# BMW_Front-Centet_Driver-Passenger_Light.net
KiCad netlist of a schematic drawn in Altium Designer
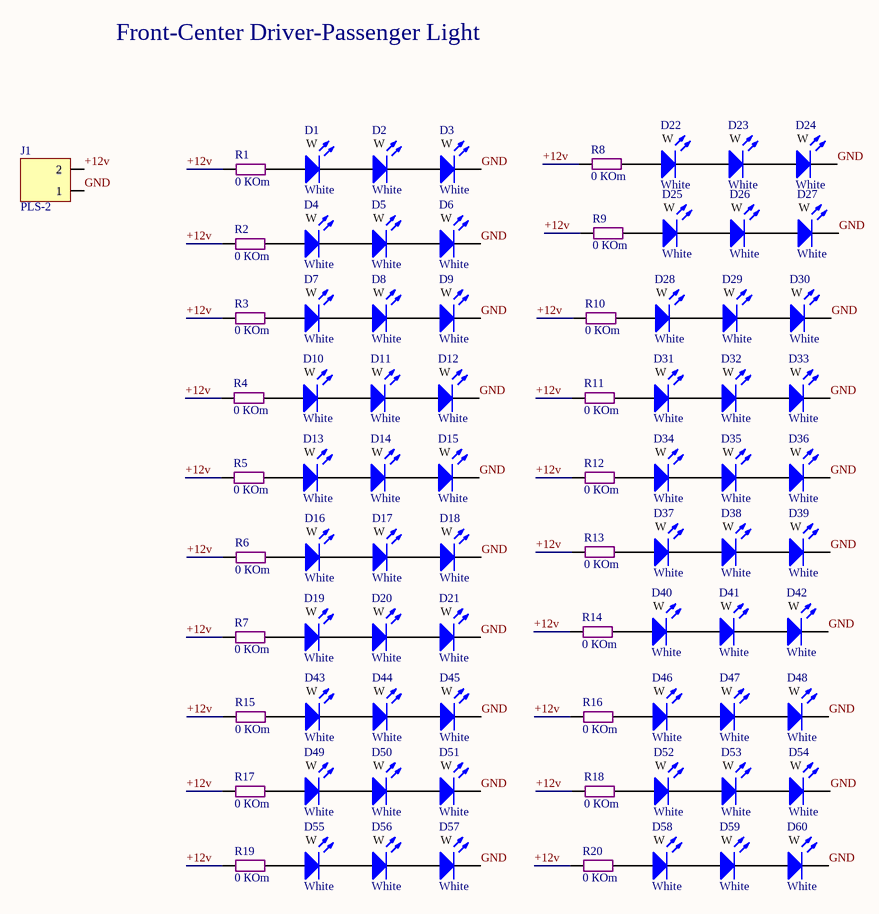
[diagram p0: BMW Front-Centet Driver-Passenger Light.SchDoc]

(export (version "E")
  (design (tool "Eeschema 10.0.6"))
  (components
    (comp (ref "D1")
      (value "White")
      (footprint "LED:LED Round 5mm White")
      (description "3.2-3.4v 25mA, 16-20cd")
      (libsource (lib "LED") (part "Led Round 5mm White"))
    )
    (comp (ref "D2")
      (value "White")
      (footprint "LED:LED Round 5mm White")
      (description "3.2-3.4v 25mA, 16-20cd")
      (libsource (lib "LED") (part "Led Round 5mm White"))
    )
    (comp (ref "D3")
      (value "White")
      (footprint "LED:LED Round 5mm White")
      (description "3.2-3.4v 25mA, 16-20cd")
      (libsource (lib "LED") (part "Led Round 5mm White"))
    )
    (comp (ref "D4")
      (value "White")
      (footprint "LED:LED Round 5mm White")
      (description "3.2-3.4v 25mA, 16-20cd")
      (libsource (lib "LED") (part "Led Round 5mm White"))
    )
    (comp (ref "D5")
      (value "White")
      (footprint "LED:LED Round 5mm White")
      (description "3.2-3.4v 25mA, 16-20cd")
      (libsource (lib "LED") (part "Led Round 5mm White"))
    )
    (comp (ref "D6")
      (value "White")
      (footprint "LED:LED Round 5mm White")
      (description "3.2-3.4v 25mA, 16-20cd")
      (libsource (lib "LED") (part "Led Round 5mm White"))
    )
    (comp (ref "D7")
      (value "White")
      (footprint "LED:LED Round 5mm White")
      (description "3.2-3.4v 25mA, 16-20cd")
      (libsource (lib "LED") (part "Led Round 5mm White"))
    )
    (comp (ref "D8")
      (value "White")
      (footprint "LED:LED Round 5mm White")
      (description "3.2-3.4v 25mA, 16-20cd")
      (libsource (lib "LED") (part "Led Round 5mm White"))
    )
    (comp (ref "D9")
      (value "White")
      (footprint "LED:LED Round 5mm White")
      (description "3.2-3.4v 25mA, 16-20cd")
      (libsource (lib "LED") (part "Led Round 5mm White"))
    )
    (comp (ref "D10")
      (value "White")
      (footprint "LED:LED Round 5mm White")
      (description "3.2-3.4v 25mA, 16-20cd")
      (libsource (lib "LED") (part "Led Round 5mm White"))
    )
    (comp (ref "D11")
      (value "White")
      (footprint "LED:LED Round 5mm White")
      (description "3.2-3.4v 25mA, 16-20cd")
      (libsource (lib "LED") (part "Led Round 5mm White"))
    )
    (comp (ref "D12")
      (value "White")
      (footprint "LED:LED Round 5mm White")
      (description "3.2-3.4v 25mA, 16-20cd")
      (libsource (lib "LED") (part "Led Round 5mm White"))
    )
    (comp (ref "D13")
      (value "White")
      (footprint "LED:LED Round 5mm White")
      (description "3.2-3.4v 25mA, 16-20cd")
      (libsource (lib "LED") (part "Led Round 5mm White"))
    )
    (comp (ref "D14")
      (value "White")
      (footprint "LED:LED Round 5mm White")
      (description "3.2-3.4v 25mA, 16-20cd")
      (libsource (lib "LED") (part "Led Round 5mm White"))
    )
    (comp (ref "D15")
      (value "White")
      (footprint "LED:LED Round 5mm White")
      (description "3.2-3.4v 25mA, 16-20cd")
      (libsource (lib "LED") (part "Led Round 5mm White"))
    )
    (comp (ref "D16")
      (value "White")
      (footprint "LED:LED Round 5mm White")
      (description "3.2-3.4v 25mA, 16-20cd")
      (libsource (lib "LED") (part "Led Round 5mm White"))
    )
    (comp (ref "D17")
      (value "White")
      (footprint "LED:LED Round 5mm White")
      (description "3.2-3.4v 25mA, 16-20cd")
      (libsource (lib "LED") (part "Led Round 5mm White"))
    )
    (comp (ref "D18")
      (value "White")
      (footprint "LED:LED Round 5mm White")
      (description "3.2-3.4v 25mA, 16-20cd")
      (libsource (lib "LED") (part "Led Round 5mm White"))
    )
    (comp (ref "D19")
      (value "White")
      (footprint "LED:LED Round 5mm White")
      (description "3.2-3.4v 25mA, 16-20cd")
      (libsource (lib "LED") (part "Led Round 5mm White"))
    )
    (comp (ref "D20")
      (value "White")
      (footprint "LED:LED Round 5mm White")
      (description "3.2-3.4v 25mA, 16-20cd")
      (libsource (lib "LED") (part "Led Round 5mm White"))
    )
    (comp (ref "D21")
      (value "White")
      (footprint "LED:LED Round 5mm White")
      (description "3.2-3.4v 25mA, 16-20cd")
      (libsource (lib "LED") (part "Led Round 5mm White"))
    )
    (comp (ref "D22")
      (value "White")
      (footprint "LED:LED Round 5mm White")
      (description "3.2-3.4v 25mA, 16-20cd")
      (libsource (lib "LED") (part "Led Round 5mm White"))
    )
    (comp (ref "D23")
      (value "White")
      (footprint "LED:LED Round 5mm White")
      (description "3.2-3.4v 25mA, 16-20cd")
      (libsource (lib "LED") (part "Led Round 5mm White"))
    )
    (comp (ref "D24")
      (value "White")
      (footprint "LED:LED Round 5mm White")
      (description "3.2-3.4v 25mA, 16-20cd")
      (libsource (lib "LED") (part "Led Round 5mm White"))
    )
    (comp (ref "D25")
      (value "White")
      (footprint "LED:LED Round 5mm White")
      (description "3.2-3.4v 25mA, 16-20cd")
      (libsource (lib "LED") (part "Led Round 5mm White"))
    )
    (comp (ref "D26")
      (value "White")
      (footprint "LED:LED Round 5mm White")
      (description "3.2-3.4v 25mA, 16-20cd")
      (libsource (lib "LED") (part "Led Round 5mm White"))
    )
    (comp (ref "D27")
      (value "White")
      (footprint "LED:LED Round 5mm White")
      (description "3.2-3.4v 25mA, 16-20cd")
      (libsource (lib "LED") (part "Led Round 5mm White"))
    )
    (comp (ref "D28")
      (value "White")
      (footprint "LED:LED Round 5mm White")
      (description "3.2-3.4v 25mA, 16-20cd")
      (libsource (lib "LED") (part "Led Round 5mm White"))
    )
    (comp (ref "D29")
      (value "White")
      (footprint "LED:LED Round 5mm White")
      (description "3.2-3.4v 25mA, 16-20cd")
      (libsource (lib "LED") (part "Led Round 5mm White"))
    )
    (comp (ref "D30")
      (value "White")
      (footprint "LED:LED Round 5mm White")
      (description "3.2-3.4v 25mA, 16-20cd")
      (libsource (lib "LED") (part "Led Round 5mm White"))
    )
    (comp (ref "D31")
      (value "White")
      (footprint "LED:LED Round 5mm White")
      (description "3.2-3.4v 25mA, 16-20cd")
      (libsource (lib "LED") (part "Led Round 5mm White"))
    )
    (comp (ref "D32")
      (value "White")
      (footprint "LED:LED Round 5mm White")
      (description "3.2-3.4v 25mA, 16-20cd")
      (libsource (lib "LED") (part "Led Round 5mm White"))
    )
    (comp (ref "D33")
      (value "White")
      (footprint "LED:LED Round 5mm White")
      (description "3.2-3.4v 25mA, 16-20cd")
      (libsource (lib "LED") (part "Led Round 5mm White"))
    )
    (comp (ref "D34")
      (value "White")
      (footprint "LED:LED Round 5mm White")
      (description "3.2-3.4v 25mA, 16-20cd")
      (libsource (lib "LED") (part "Led Round 5mm White"))
    )
    (comp (ref "D35")
      (value "White")
      (footprint "LED:LED Round 5mm White")
      (description "3.2-3.4v 25mA, 16-20cd")
      (libsource (lib "LED") (part "Led Round 5mm White"))
    )
    (comp (ref "D36")
      (value "White")
      (footprint "LED:LED Round 5mm White")
      (description "3.2-3.4v 25mA, 16-20cd")
      (libsource (lib "LED") (part "Led Round 5mm White"))
    )
    (comp (ref "D37")
      (value "White")
      (footprint "LED:LED Round 5mm White")
      (description "3.2-3.4v 25mA, 16-20cd")
      (libsource (lib "LED") (part "Led Round 5mm White"))
    )
    (comp (ref "D38")
      (value "White")
      (footprint "LED:LED Round 5mm White")
      (description "3.2-3.4v 25mA, 16-20cd")
      (libsource (lib "LED") (part "Led Round 5mm White"))
    )
    (comp (ref "D39")
      (value "White")
      (footprint "LED:LED Round 5mm White")
      (description "3.2-3.4v 25mA, 16-20cd")
      (libsource (lib "LED") (part "Led Round 5mm White"))
    )
    (comp (ref "D40")
      (value "White")
      (footprint "LED:LED Round 5mm White")
      (description "3.2-3.4v 25mA, 16-20cd")
      (libsource (lib "LED") (part "Led Round 5mm White"))
    )
    (comp (ref "D41")
      (value "White")
      (footprint "LED:LED Round 5mm White")
      (description "3.2-3.4v 25mA, 16-20cd")
      (libsource (lib "LED") (part "Led Round 5mm White"))
    )
    (comp (ref "D42")
      (value "White")
      (footprint "LED:LED Round 5mm White")
      (description "3.2-3.4v 25mA, 16-20cd")
      (libsource (lib "LED") (part "Led Round 5mm White"))
    )
    (comp (ref "D43")
      (value "White")
      (footprint "LED:LED Round 5mm White")
      (description "3.2-3.4v 25mA, 16-20cd")
      (libsource (lib "LED") (part "Led Round 5mm White"))
    )
    (comp (ref "D44")
      (value "White")
      (footprint "LED:LED Round 5mm White")
      (description "3.2-3.4v 25mA, 16-20cd")
      (libsource (lib "LED") (part "Led Round 5mm White"))
    )
    (comp (ref "D45")
      (value "White")
      (footprint "LED:LED Round 5mm White")
      (description "3.2-3.4v 25mA, 16-20cd")
      (libsource (lib "LED") (part "Led Round 5mm White"))
    )
    (comp (ref "D46")
      (value "White")
      (footprint "LED:LED Round 5mm White")
      (description "3.2-3.4v 25mA, 16-20cd")
      (libsource (lib "LED") (part "Led Round 5mm White"))
    )
    (comp (ref "D47")
      (value "White")
      (footprint "LED:LED Round 5mm White")
      (description "3.2-3.4v 25mA, 16-20cd")
      (libsource (lib "LED") (part "Led Round 5mm White"))
    )
    (comp (ref "D48")
      (value "White")
      (footprint "LED:LED Round 5mm White")
      (description "3.2-3.4v 25mA, 16-20cd")
      (libsource (lib "LED") (part "Led Round 5mm White"))
    )
    (comp (ref "D49")
      (value "White")
      (footprint "LED:LED Round 5mm White")
      (description "3.2-3.4v 25mA, 16-20cd")
      (libsource (lib "LED") (part "Led Round 5mm White"))
    )
    (comp (ref "D50")
      (value "White")
      (footprint "LED:LED Round 5mm White")
      (description "3.2-3.4v 25mA, 16-20cd")
      (libsource (lib "LED") (part "Led Round 5mm White"))
    )
    (comp (ref "D51")
      (value "White")
      (footprint "LED:LED Round 5mm White")
      (description "3.2-3.4v 25mA, 16-20cd")
      (libsource (lib "LED") (part "Led Round 5mm White"))
    )
    (comp (ref "D52")
      (value "White")
      (footprint "LED:LED Round 5mm White")
      (description "3.2-3.4v 25mA, 16-20cd")
      (libsource (lib "LED") (part "Led Round 5mm White"))
    )
    (comp (ref "D53")
      (value "White")
      (footprint "LED:LED Round 5mm White")
      (description "3.2-3.4v 25mA, 16-20cd")
      (libsource (lib "LED") (part "Led Round 5mm White"))
    )
    (comp (ref "D54")
      (value "White")
      (footprint "LED:LED Round 5mm White")
      (description "3.2-3.4v 25mA, 16-20cd")
      (libsource (lib "LED") (part "Led Round 5mm White"))
    )
    (comp (ref "D55")
      (value "White")
      (footprint "LED:LED Round 5mm White")
      (description "3.2-3.4v 25mA, 16-20cd")
      (libsource (lib "LED") (part "Led Round 5mm White"))
    )
    (comp (ref "D56")
      (value "White")
      (footprint "LED:LED Round 5mm White")
      (description "3.2-3.4v 25mA, 16-20cd")
      (libsource (lib "LED") (part "Led Round 5mm White"))
    )
    (comp (ref "D57")
      (value "White")
      (footprint "LED:LED Round 5mm White")
      (description "3.2-3.4v 25mA, 16-20cd")
      (libsource (lib "LED") (part "Led Round 5mm White"))
    )
    (comp (ref "D58")
      (value "White")
      (footprint "LED:LED Round 5mm White")
      (description "3.2-3.4v 25mA, 16-20cd")
      (libsource (lib "LED") (part "Led Round 5mm White"))
    )
    (comp (ref "D59")
      (value "White")
      (footprint "LED:LED Round 5mm White")
      (description "3.2-3.4v 25mA, 16-20cd")
      (libsource (lib "LED") (part "Led Round 5mm White"))
    )
    (comp (ref "D60")
      (value "White")
      (footprint "LED:LED Round 5mm White")
      (description "3.2-3.4v 25mA, 16-20cd")
      (libsource (lib "LED") (part "Led Round 5mm White"))
    )
    (comp (ref "J1")
      (value "PLS-2")
      (footprint "Connector:Line 2.54 x 2")
      (description "Vert, Sgl line, Male")
      (libsource (lib "Connector") (part "PLS-2"))
    )
    (comp (ref "R1")
      (value "0 КOm")
      (footprint "bj Lib:SMD 0603 (1608)")
      (libsource (lib "ss_ServersControl") (part "Resistor"))
    )
    (comp (ref "R2")
      (value "0 КOm")
      (footprint "bj Lib:SMD 0603 (1608)")
      (libsource (lib "ss_ServersControl") (part "Resistor"))
    )
    (comp (ref "R3")
      (value "0 КOm")
      (footprint "bj Lib:SMD 0603 (1608)")
      (libsource (lib "ss_ServersControl") (part "Resistor"))
    )
    (comp (ref "R4")
      (value "0 КOm")
      (footprint "bj Lib:SMD 0603 (1608)")
      (libsource (lib "ss_ServersControl") (part "Resistor"))
    )
    (comp (ref "R5")
      (value "0 КOm")
      (footprint "bj Lib:SMD 0603 (1608)")
      (libsource (lib "ss_ServersControl") (part "Resistor"))
    )
    (comp (ref "R6")
      (value "0 КOm")
      (footprint "bj Lib:SMD 0603 (1608)")
      (libsource (lib "ss_ServersControl") (part "Resistor"))
    )
    (comp (ref "R7")
      (value "0 КOm")
      (footprint "bj Lib:SMD 0603 (1608)")
      (libsource (lib "ss_ServersControl") (part "Resistor"))
    )
    (comp (ref "R8")
      (value "0 КOm")
      (footprint "bj Lib:SMD 0603 (1608)")
      (libsource (lib "ss_ServersControl") (part "Resistor"))
    )
    (comp (ref "R9")
      (value "0 КOm")
      (footprint "bj Lib:SMD 0603 (1608)")
      (libsource (lib "ss_ServersControl") (part "Resistor"))
    )
    (comp (ref "R10")
      (value "0 КOm")
      (footprint "bj Lib:SMD 0603 (1608)")
      (libsource (lib "ss_ServersControl") (part "Resistor"))
    )
    (comp (ref "R11")
      (value "0 КOm")
      (footprint "bj Lib:SMD 0603 (1608)")
      (libsource (lib "ss_ServersControl") (part "Resistor"))
    )
    (comp (ref "R12")
      (value "0 КOm")
      (footprint "bj Lib:SMD 0603 (1608)")
      (libsource (lib "ss_ServersControl") (part "Resistor"))
    )
    (comp (ref "R13")
      (value "0 КOm")
      (footprint "bj Lib:SMD 0603 (1608)")
      (libsource (lib "ss_ServersControl") (part "Resistor"))
    )
    (comp (ref "R14")
      (value "0 КOm")
      (footprint "bj Lib:SMD 0603 (1608)")
      (libsource (lib "ss_ServersControl") (part "Resistor"))
    )
    (comp (ref "R15")
      (value "0 КOm")
      (footprint "bj Lib:SMD 0603 (1608)")
      (libsource (lib "ss_ServersControl") (part "Resistor"))
    )
    (comp (ref "R16")
      (value "0 КOm")
      (footprint "bj Lib:SMD 0603 (1608)")
      (libsource (lib "ss_ServersControl") (part "Resistor"))
    )
    (comp (ref "R17")
      (value "0 КOm")
      (footprint "bj Lib:SMD 0603 (1608)")
      (libsource (lib "ss_ServersControl") (part "Resistor"))
    )
    (comp (ref "R18")
      (value "0 КOm")
      (footprint "bj Lib:SMD 0603 (1608)")
      (libsource (lib "ss_ServersControl") (part "Resistor"))
    )
    (comp (ref "R19")
      (value "0 КOm")
      (footprint "bj Lib:SMD 0603 (1608)")
      (libsource (lib "ss_ServersControl") (part "Resistor"))
    )
    (comp (ref "R20")
      (value "0 КOm")
      (footprint "bj Lib:SMD 0603 (1608)")
      (libsource (lib "ss_ServersControl") (part "Resistor"))
    )
  )
  (nets
    (net (code "1") (name "/+12v") (class "Default")
      (node (ref "J1") (pin "2") (pinfunction "2_2") (pintype "passive"))
      (node (ref "R1") (pin "1") (pinfunction "1_1") (pintype "passive"))
      (node (ref "R10") (pin "1") (pinfunction "1_1") (pintype "passive"))
      (node (ref "R11") (pin "1") (pinfunction "1_1") (pintype "passive"))
      (node (ref "R12") (pin "1") (pinfunction "1_1") (pintype "passive"))
      (node (ref "R13") (pin "1") (pinfunction "1_1") (pintype "passive"))
      (node (ref "R14") (pin "1") (pinfunction "1_1") (pintype "passive"))
      (node (ref "R15") (pin "1") (pinfunction "1_1") (pintype "passive"))
      (node (ref "R16") (pin "1") (pinfunction "1_1") (pintype "passive"))
      (node (ref "R17") (pin "1") (pinfunction "1_1") (pintype "passive"))
      (node (ref "R18") (pin "1") (pinfunction "1_1") (pintype "passive"))
      (node (ref "R19") (pin "1") (pinfunction "1_1") (pintype "passive"))
      (node (ref "R2") (pin "1") (pinfunction "1_1") (pintype "passive"))
      (node (ref "R20") (pin "1") (pinfunction "1_1") (pintype "passive"))
      (node (ref "R3") (pin "1") (pinfunction "1_1") (pintype "passive"))
      (node (ref "R4") (pin "1") (pinfunction "1_1") (pintype "passive"))
      (node (ref "R5") (pin "1") (pinfunction "1_1") (pintype "passive"))
      (node (ref "R6") (pin "1") (pinfunction "1_1") (pintype "passive"))
      (node (ref "R7") (pin "1") (pinfunction "1_1") (pintype "passive"))
      (node (ref "R8") (pin "1") (pinfunction "1_1") (pintype "passive"))
      (node (ref "R9") (pin "1") (pinfunction "1_1") (pintype "passive"))
    )
    (net (code "2") (name "/GND") (class "Default")
      (node (ref "D12") (pin "K") (pinfunction "K_K") (pintype "passive"))
      (node (ref "D15") (pin "K") (pinfunction "K_K") (pintype "passive"))
      (node (ref "D18") (pin "K") (pinfunction "K_K") (pintype "passive"))
      (node (ref "D21") (pin "K") (pinfunction "K_K") (pintype "passive"))
      (node (ref "D24") (pin "K") (pinfunction "K_K") (pintype "passive"))
      (node (ref "D27") (pin "K") (pinfunction "K_K") (pintype "passive"))
      (node (ref "D3") (pin "K") (pinfunction "K_K") (pintype "passive"))
      (node (ref "D30") (pin "K") (pinfunction "K_K") (pintype "passive"))
      (node (ref "D33") (pin "K") (pinfunction "K_K") (pintype "passive"))
      (node (ref "D36") (pin "K") (pinfunction "K_K") (pintype "passive"))
      (node (ref "D39") (pin "K") (pinfunction "K_K") (pintype "passive"))
      (node (ref "D42") (pin "K") (pinfunction "K_K") (pintype "passive"))
      (node (ref "D45") (pin "K") (pinfunction "K_K") (pintype "passive"))
      (node (ref "D48") (pin "K") (pinfunction "K_K") (pintype "passive"))
      (node (ref "D51") (pin "K") (pinfunction "K_K") (pintype "passive"))
      (node (ref "D54") (pin "K") (pinfunction "K_K") (pintype "passive"))
      (node (ref "D57") (pin "K") (pinfunction "K_K") (pintype "passive"))
      (node (ref "D6") (pin "K") (pinfunction "K_K") (pintype "passive"))
      (node (ref "D60") (pin "K") (pinfunction "K_K") (pintype "passive"))
      (node (ref "D9") (pin "K") (pinfunction "K_K") (pintype "passive"))
      (node (ref "J1") (pin "1") (pinfunction "1_1") (pintype "passive"))
    )
    (net (code "3") (name "Net-(D1-PadA)") (class "Default")
      (node (ref "D1") (pin "A") (pinfunction "A_A") (pintype "passive"))
      (node (ref "R1") (pin "2") (pinfunction "2_2") (pintype "passive"))
    )
    (net (code "4") (name "Net-(D1-PadK)") (class "Default")
      (node (ref "D1") (pin "K") (pinfunction "K_K") (pintype "passive"))
      (node (ref "D2") (pin "A") (pinfunction "A_A") (pintype "passive"))
    )
    (net (code "5") (name "Net-(D2-PadK)") (class "Default")
      (node (ref "D2") (pin "K") (pinfunction "K_K") (pintype "passive"))
      (node (ref "D3") (pin "A") (pinfunction "A_A") (pintype "passive"))
    )
    (net (code "6") (name "Net-(D4-PadA)") (class "Default")
      (node (ref "D4") (pin "A") (pinfunction "A_A") (pintype "passive"))
      (node (ref "R2") (pin "2") (pinfunction "2_2") (pintype "passive"))
    )
    (net (code "7") (name "Net-(D4-PadK)") (class "Default")
      (node (ref "D4") (pin "K") (pinfunction "K_K") (pintype "passive"))
      (node (ref "D5") (pin "A") (pinfunction "A_A") (pintype "passive"))
    )
    (net (code "8") (name "Net-(D5-PadK)") (class "Default")
      (node (ref "D5") (pin "K") (pinfunction "K_K") (pintype "passive"))
      (node (ref "D6") (pin "A") (pinfunction "A_A") (pintype "passive"))
    )
    (net (code "9") (name "Net-(D7-PadA)") (class "Default")
      (node (ref "D7") (pin "A") (pinfunction "A_A") (pintype "passive"))
      (node (ref "R3") (pin "2") (pinfunction "2_2") (pintype "passive"))
    )
    (net (code "10") (name "Net-(D7-PadK)") (class "Default")
      (node (ref "D7") (pin "K") (pinfunction "K_K") (pintype "passive"))
      (node (ref "D8") (pin "A") (pinfunction "A_A") (pintype "passive"))
    )
    (net (code "11") (name "Net-(D8-PadK)") (class "Default")
      (node (ref "D8") (pin "K") (pinfunction "K_K") (pintype "passive"))
      (node (ref "D9") (pin "A") (pinfunction "A_A") (pintype "passive"))
    )
    (net (code "12") (name "Net-(D10-PadA)") (class "Default")
      (node (ref "D10") (pin "A") (pinfunction "A_A") (pintype "passive"))
      (node (ref "R4") (pin "2") (pinfunction "2_2") (pintype "passive"))
    )
    (net (code "13") (name "Net-(D10-PadK)") (class "Default")
      (node (ref "D10") (pin "K") (pinfunction "K_K") (pintype "passive"))
      (node (ref "D11") (pin "A") (pinfunction "A_A") (pintype "passive"))
    )
    (net (code "14") (name "Net-(D11-PadK)") (class "Default")
      (node (ref "D11") (pin "K") (pinfunction "K_K") (pintype "passive"))
      (node (ref "D12") (pin "A") (pinfunction "A_A") (pintype "passive"))
    )
    (net (code "15") (name "Net-(D13-PadA)") (class "Default")
      (node (ref "D13") (pin "A") (pinfunction "A_A") (pintype "passive"))
      (node (ref "R5") (pin "2") (pinfunction "2_2") (pintype "passive"))
    )
    (net (code "16") (name "Net-(D13-PadK)") (class "Default")
      (node (ref "D13") (pin "K") (pinfunction "K_K") (pintype "passive"))
      (node (ref "D14") (pin "A") (pinfunction "A_A") (pintype "passive"))
    )
    (net (code "17") (name "Net-(D14-PadK)") (class "Default")
      (node (ref "D14") (pin "K") (pinfunction "K_K") (pintype "passive"))
      (node (ref "D15") (pin "A") (pinfunction "A_A") (pintype "passive"))
    )
    (net (code "18") (name "Net-(D16-PadA)") (class "Default")
      (node (ref "D16") (pin "A") (pinfunction "A_A") (pintype "passive"))
      (node (ref "R6") (pin "2") (pinfunction "2_2") (pintype "passive"))
    )
    (net (code "19") (name "Net-(D16-PadK)") (class "Default")
      (node (ref "D16") (pin "K") (pinfunction "K_K") (pintype "passive"))
      (node (ref "D17") (pin "A") (pinfunction "A_A") (pintype "passive"))
    )
    (net (code "20") (name "Net-(D17-PadK)") (class "Default")
      (node (ref "D17") (pin "K") (pinfunction "K_K") (pintype "passive"))
      (node (ref "D18") (pin "A") (pinfunction "A_A") (pintype "passive"))
    )
    (net (code "21") (name "Net-(D19-PadA)") (class "Default")
      (node (ref "D19") (pin "A") (pinfunction "A_A") (pintype "passive"))
      (node (ref "R7") (pin "2") (pinfunction "2_2") (pintype "passive"))
    )
    (net (code "22") (name "Net-(D19-PadK)") (class "Default")
      (node (ref "D19") (pin "K") (pinfunction "K_K") (pintype "passive"))
      (node (ref "D20") (pin "A") (pinfunction "A_A") (pintype "passive"))
    )
    (net (code "23") (name "Net-(D20-PadK)") (class "Default")
      (node (ref "D20") (pin "K") (pinfunction "K_K") (pintype "passive"))
      (node (ref "D21") (pin "A") (pinfunction "A_A") (pintype "passive"))
    )
    (net (code "24") (name "Net-(D22-PadA)") (class "Default")
      (node (ref "D22") (pin "A") (pinfunction "A_A") (pintype "passive"))
      (node (ref "R8") (pin "2") (pinfunction "2_2") (pintype "passive"))
    )
    (net (code "25") (name "Net-(D22-PadK)") (class "Default")
      (node (ref "D22") (pin "K") (pinfunction "K_K") (pintype "passive"))
      (node (ref "D23") (pin "A") (pinfunction "A_A") (pintype "passive"))
    )
    (net (code "26") (name "Net-(D23-PadK)") (class "Default")
      (node (ref "D23") (pin "K") (pinfunction "K_K") (pintype "passive"))
      (node (ref "D24") (pin "A") (pinfunction "A_A") (pintype "passive"))
    )
    (net (code "27") (name "Net-(D25-PadA)") (class "Default")
      (node (ref "D25") (pin "A") (pinfunction "A_A") (pintype "passive"))
      (node (ref "R9") (pin "2") (pinfunction "2_2") (pintype "passive"))
    )
    (net (code "28") (name "Net-(D25-PadK)") (class "Default")
      (node (ref "D25") (pin "K") (pinfunction "K_K") (pintype "passive"))
      (node (ref "D26") (pin "A") (pinfunction "A_A") (pintype "passive"))
    )
    (net (code "29") (name "Net-(D26-PadK)") (class "Default")
      (node (ref "D26") (pin "K") (pinfunction "K_K") (pintype "passive"))
      (node (ref "D27") (pin "A") (pinfunction "A_A") (pintype "passive"))
    )
    (net (code "30") (name "Net-(D28-PadA)") (class "Default")
      (node (ref "D28") (pin "A") (pinfunction "A_A") (pintype "passive"))
      (node (ref "R10") (pin "2") (pinfunction "2_2") (pintype "passive"))
    )
    (net (code "31") (name "Net-(D28-PadK)") (class "Default")
      (node (ref "D28") (pin "K") (pinfunction "K_K") (pintype "passive"))
      (node (ref "D29") (pin "A") (pinfunction "A_A") (pintype "passive"))
    )
    (net (code "32") (name "Net-(D29-PadK)") (class "Default")
      (node (ref "D29") (pin "K") (pinfunction "K_K") (pintype "passive"))
      (node (ref "D30") (pin "A") (pinfunction "A_A") (pintype "passive"))
    )
    (net (code "33") (name "Net-(D31-PadA)") (class "Default")
      (node (ref "D31") (pin "A") (pinfunction "A_A") (pintype "passive"))
      (node (ref "R11") (pin "2") (pinfunction "2_2") (pintype "passive"))
    )
    (net (code "34") (name "Net-(D31-PadK)") (class "Default")
      (node (ref "D31") (pin "K") (pinfunction "K_K") (pintype "passive"))
      (node (ref "D32") (pin "A") (pinfunction "A_A") (pintype "passive"))
    )
    (net (code "35") (name "Net-(D32-PadK)") (class "Default")
      (node (ref "D32") (pin "K") (pinfunction "K_K") (pintype "passive"))
      (node (ref "D33") (pin "A") (pinfunction "A_A") (pintype "passive"))
    )
    (net (code "36") (name "Net-(D34-PadA)") (class "Default")
      (node (ref "D34") (pin "A") (pinfunction "A_A") (pintype "passive"))
      (node (ref "R12") (pin "2") (pinfunction "2_2") (pintype "passive"))
    )
    (net (code "37") (name "Net-(D34-PadK)") (class "Default")
      (node (ref "D34") (pin "K") (pinfunction "K_K") (pintype "passive"))
      (node (ref "D35") (pin "A") (pinfunction "A_A") (pintype "passive"))
    )
    (net (code "38") (name "Net-(D35-PadK)") (class "Default")
      (node (ref "D35") (pin "K") (pinfunction "K_K") (pintype "passive"))
      (node (ref "D36") (pin "A") (pinfunction "A_A") (pintype "passive"))
    )
    (net (code "39") (name "Net-(D37-PadA)") (class "Default")
      (node (ref "D37") (pin "A") (pinfunction "A_A") (pintype "passive"))
      (node (ref "R13") (pin "2") (pinfunction "2_2") (pintype "passive"))
    )
    (net (code "40") (name "Net-(D37-PadK)") (class "Default")
      (node (ref "D37") (pin "K") (pinfunction "K_K") (pintype "passive"))
      (node (ref "D38") (pin "A") (pinfunction "A_A") (pintype "passive"))
    )
    (net (code "41") (name "Net-(D38-PadK)") (class "Default")
      (node (ref "D38") (pin "K") (pinfunction "K_K") (pintype "passive"))
      (node (ref "D39") (pin "A") (pinfunction "A_A") (pintype "passive"))
    )
    (net (code "42") (name "Net-(D40-PadA)") (class "Default")
      (node (ref "D40") (pin "A") (pinfunction "A_A") (pintype "passive"))
      (node (ref "R14") (pin "2") (pinfunction "2_2") (pintype "passive"))
    )
    (net (code "43") (name "Net-(D40-PadK)") (class "Default")
      (node (ref "D40") (pin "K") (pinfunction "K_K") (pintype "passive"))
      (node (ref "D41") (pin "A") (pinfunction "A_A") (pintype "passive"))
    )
    (net (code "44") (name "Net-(D41-PadK)") (class "Default")
      (node (ref "D41") (pin "K") (pinfunction "K_K") (pintype "passive"))
      (node (ref "D42") (pin "A") (pinfunction "A_A") (pintype "passive"))
    )
    (net (code "45") (name "Net-(D43-PadA)") (class "Default")
      (node (ref "D43") (pin "A") (pinfunction "A_A") (pintype "passive"))
      (node (ref "R15") (pin "2") (pinfunction "2_2") (pintype "passive"))
    )
    (net (code "46") (name "Net-(D43-PadK)") (class "Default")
      (node (ref "D43") (pin "K") (pinfunction "K_K") (pintype "passive"))
      (node (ref "D44") (pin "A") (pinfunction "A_A") (pintype "passive"))
    )
    (net (code "47") (name "Net-(D44-PadK)") (class "Default")
      (node (ref "D44") (pin "K") (pinfunction "K_K") (pintype "passive"))
      (node (ref "D45") (pin "A") (pinfunction "A_A") (pintype "passive"))
    )
    (net (code "48") (name "Net-(D46-PadA)") (class "Default")
      (node (ref "D46") (pin "A") (pinfunction "A_A") (pintype "passive"))
      (node (ref "R16") (pin "2") (pinfunction "2_2") (pintype "passive"))
    )
    (net (code "49") (name "Net-(D46-PadK)") (class "Default")
      (node (ref "D46") (pin "K") (pinfunction "K_K") (pintype "passive"))
      (node (ref "D47") (pin "A") (pinfunction "A_A") (pintype "passive"))
    )
    (net (code "50") (name "Net-(D47-PadK)") (class "Default")
      (node (ref "D47") (pin "K") (pinfunction "K_K") (pintype "passive"))
      (node (ref "D48") (pin "A") (pinfunction "A_A") (pintype "passive"))
    )
    (net (code "51") (name "Net-(D49-PadA)") (class "Default")
      (node (ref "D49") (pin "A") (pinfunction "A_A") (pintype "passive"))
      (node (ref "R17") (pin "2") (pinfunction "2_2") (pintype "passive"))
    )
    (net (code "52") (name "Net-(D49-PadK)") (class "Default")
      (node (ref "D49") (pin "K") (pinfunction "K_K") (pintype "passive"))
      (node (ref "D50") (pin "A") (pinfunction "A_A") (pintype "passive"))
    )
    (net (code "53") (name "Net-(D50-PadK)") (class "Default")
      (node (ref "D50") (pin "K") (pinfunction "K_K") (pintype "passive"))
      (node (ref "D51") (pin "A") (pinfunction "A_A") (pintype "passive"))
    )
    (net (code "54") (name "Net-(D52-PadA)") (class "Default")
      (node (ref "D52") (pin "A") (pinfunction "A_A") (pintype "passive"))
      (node (ref "R18") (pin "2") (pinfunction "2_2") (pintype "passive"))
    )
    (net (code "55") (name "Net-(D52-PadK)") (class "Default")
      (node (ref "D52") (pin "K") (pinfunction "K_K") (pintype "passive"))
      (node (ref "D53") (pin "A") (pinfunction "A_A") (pintype "passive"))
    )
    (net (code "56") (name "Net-(D53-PadK)") (class "Default")
      (node (ref "D53") (pin "K") (pinfunction "K_K") (pintype "passive"))
      (node (ref "D54") (pin "A") (pinfunction "A_A") (pintype "passive"))
    )
    (net (code "57") (name "Net-(D55-PadA)") (class "Default")
      (node (ref "D55") (pin "A") (pinfunction "A_A") (pintype "passive"))
      (node (ref "R19") (pin "2") (pinfunction "2_2") (pintype "passive"))
    )
    (net (code "58") (name "Net-(D55-PadK)") (class "Default")
      (node (ref "D55") (pin "K") (pinfunction "K_K") (pintype "passive"))
      (node (ref "D56") (pin "A") (pinfunction "A_A") (pintype "passive"))
    )
    (net (code "59") (name "Net-(D56-PadK)") (class "Default")
      (node (ref "D56") (pin "K") (pinfunction "K_K") (pintype "passive"))
      (node (ref "D57") (pin "A") (pinfunction "A_A") (pintype "passive"))
    )
    (net (code "60") (name "Net-(D58-PadA)") (class "Default")
      (node (ref "D58") (pin "A") (pinfunction "A_A") (pintype "passive"))
      (node (ref "R20") (pin "2") (pinfunction "2_2") (pintype "passive"))
    )
    (net (code "61") (name "Net-(D58-PadK)") (class "Default")
      (node (ref "D58") (pin "K") (pinfunction "K_K") (pintype "passive"))
      (node (ref "D59") (pin "A") (pinfunction "A_A") (pintype "passive"))
    )
    (net (code "62") (name "Net-(D59-PadK)") (class "Default")
      (node (ref "D59") (pin "K") (pinfunction "K_K") (pintype "passive"))
      (node (ref "D60") (pin "A") (pinfunction "A_A") (pintype "passive"))
    )
  )
)
